# CutMonitor_PressureSensor.net
KiCad netlist of a schematic drawn in Altium Designer
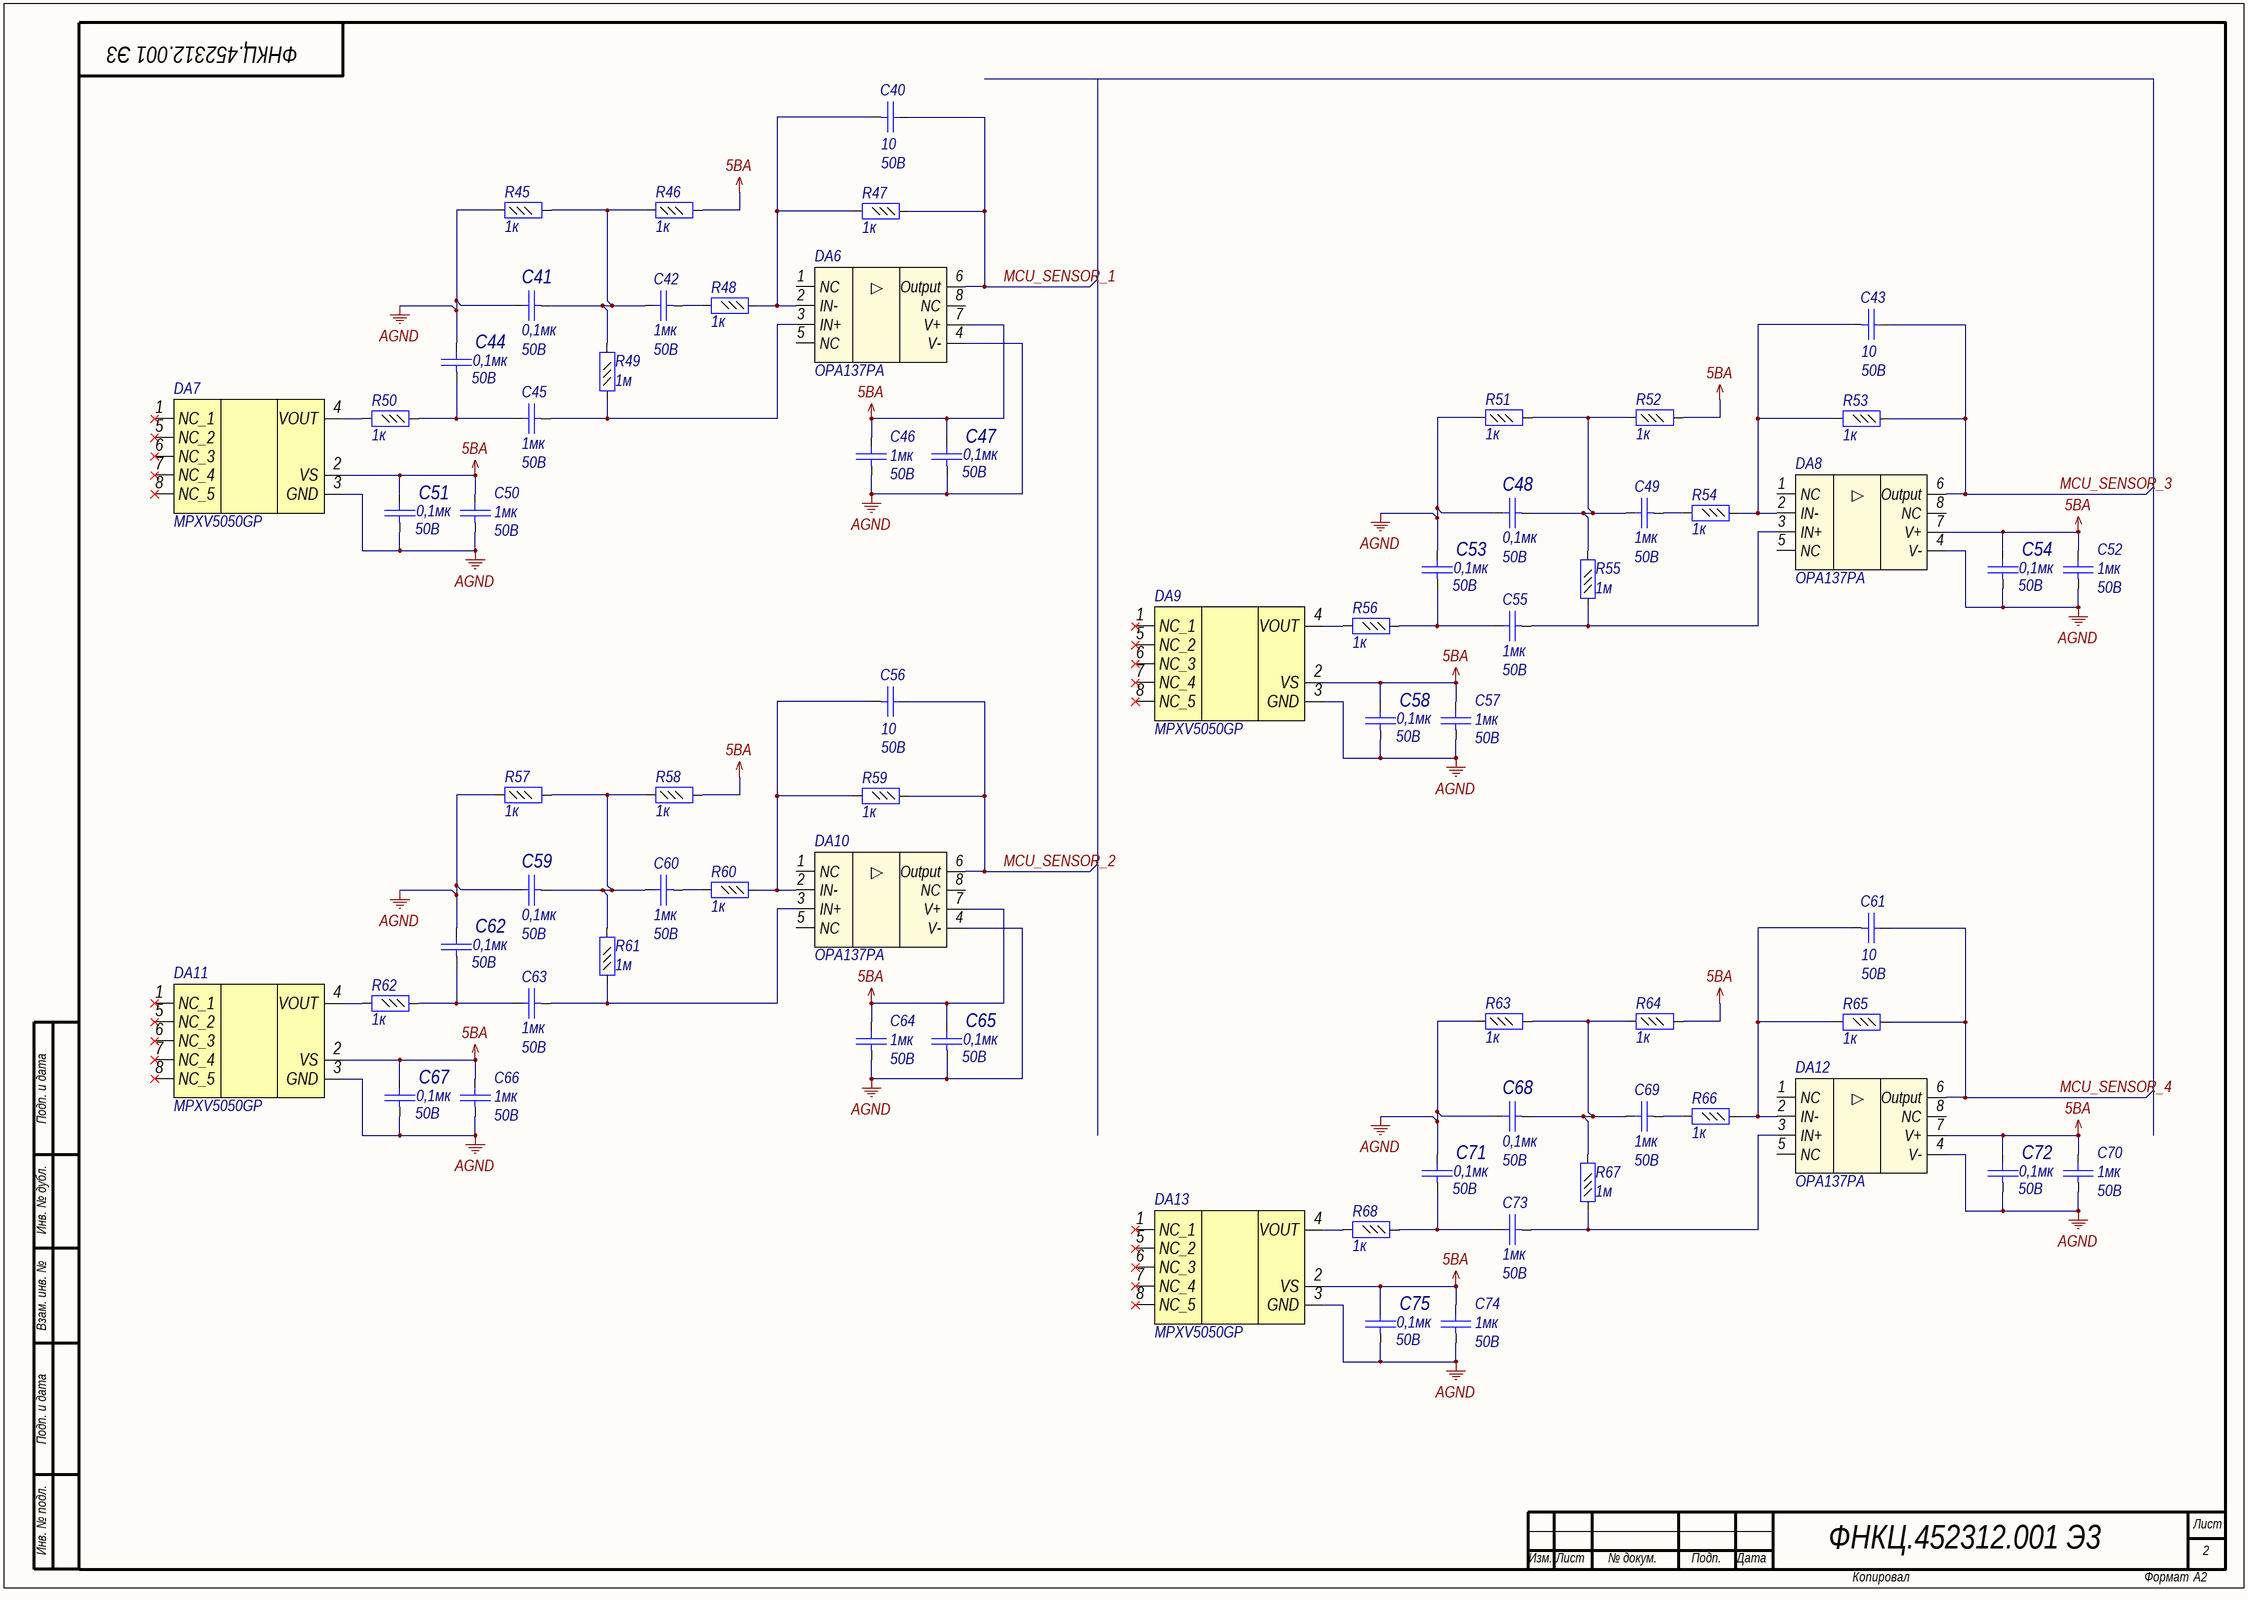
[diagram p0: CutMonitor_PressureSensor.SchDoc]

(export (version "E")
  (design (tool "Eeschema 10.0.6"))
  (components
    (comp (ref "C40")
      (value "10")
      (footprint "C0603")
      (description "Конденсатор")
      (fields
        (field (name "VOLTAGE") "50B")
        (field (name "PART NUMBER") "GRM1885C1H100J")
        (field (name "Comment") "Capacitor")
      )
      (libsource (lib "MOP44") (part "Capacitor"))
    )
    (comp (ref "C41")
      (value "0,1мк")
      (footprint "C0603")
      (description "Конденсатор")
      (fields
        (field (name "VOLTAGE") "50B")
        (field (name "PART NUMBER") "GRM188R71H104KA93D")
        (field (name "Comment") "Capacitor")
      )
      (libsource (lib "MOP44") (part "Capacitor"))
    )
    (comp (ref "C42")
      (value "1мк")
      (footprint "C0805")
      (description "Конденсатор")
      (fields
        (field (name "VOLTAGE") "50B")
        (field (name "PART NUMBER") "GRM21BR71H105K")
        (field (name "Comment") "Capacitor")
      )
      (libsource (lib "MOP44") (part "Capacitor"))
    )
    (comp (ref "C43")
      (value "10")
      (footprint "C0603")
      (description "Конденсатор")
      (fields
        (field (name "VOLTAGE") "50B")
        (field (name "PART NUMBER") "GRM1885C1H100J")
        (field (name "Comment") "Capacitor")
      )
      (libsource (lib "MOP44") (part "Capacitor"))
    )
    (comp (ref "C44")
      (value "0,1мк")
      (footprint "C0603")
      (description "Конденсатор")
      (fields
        (field (name "VOLTAGE") "50B")
        (field (name "PART NUMBER") "GRM188R71H104KA93D")
        (field (name "Comment") "Capacitor")
      )
      (libsource (lib "MOP44") (part "Capacitor"))
    )
    (comp (ref "C45")
      (value "1мк")
      (footprint "C0805")
      (description "Конденсатор")
      (fields
        (field (name "VOLTAGE") "50B")
        (field (name "PART NUMBER") "GRM21BR71H105K")
        (field (name "Comment") "Capacitor")
      )
      (libsource (lib "MOP44") (part "Capacitor"))
    )
    (comp (ref "C46")
      (value "1мк")
      (footprint "C0805")
      (description "Конденсатор")
      (fields
        (field (name "VOLTAGE") "50B")
        (field (name "PART NUMBER") "GRM21BR71H105K")
        (field (name "Comment") "Capacitor")
      )
      (libsource (lib "MOP44") (part "Capacitor"))
    )
    (comp (ref "C47")
      (value "0,1мк")
      (footprint "C0603")
      (description "Конденсатор")
      (fields
        (field (name "VOLTAGE") "50B")
        (field (name "PART NUMBER") "GRM188R71H104KA93D")
        (field (name "Comment") "Capacitor")
      )
      (libsource (lib "MOP44") (part "Capacitor"))
    )
    (comp (ref "C48")
      (value "0,1мк")
      (footprint "C0603")
      (description "Конденсатор")
      (fields
        (field (name "VOLTAGE") "50B")
        (field (name "PART NUMBER") "GRM188R71H104KA93D")
        (field (name "Comment") "Capacitor")
      )
      (libsource (lib "MOP44") (part "Capacitor"))
    )
    (comp (ref "C49")
      (value "1мк")
      (footprint "C0805")
      (description "Конденсатор")
      (fields
        (field (name "VOLTAGE") "50B")
        (field (name "PART NUMBER") "GRM21BR71H105K")
        (field (name "Comment") "Capacitor")
      )
      (libsource (lib "MOP44") (part "Capacitor"))
    )
    (comp (ref "C50")
      (value "1мк")
      (footprint "C0805")
      (description "Конденсатор")
      (fields
        (field (name "VOLTAGE") "50B")
        (field (name "PART NUMBER") "GRM21BR71H105K")
        (field (name "Comment") "Capacitor")
      )
      (libsource (lib "MOP44") (part "Capacitor"))
    )
    (comp (ref "C51")
      (value "0,1мк")
      (footprint "C0603")
      (description "Конденсатор")
      (fields
        (field (name "VOLTAGE") "50B")
        (field (name "PART NUMBER") "GRM188R71H104KA93D")
        (field (name "Comment") "Capacitor")
      )
      (libsource (lib "MOP44") (part "Capacitor"))
    )
    (comp (ref "C52")
      (value "1мк")
      (footprint "C0805")
      (description "Конденсатор")
      (fields
        (field (name "VOLTAGE") "50B")
        (field (name "PART NUMBER") "GRM21BR71H105K")
        (field (name "Comment") "Capacitor")
      )
      (libsource (lib "MOP44") (part "Capacitor"))
    )
    (comp (ref "C53")
      (value "0,1мк")
      (footprint "C0603")
      (description "Конденсатор")
      (fields
        (field (name "VOLTAGE") "50B")
        (field (name "PART NUMBER") "GRM188R71H104KA93D")
        (field (name "Comment") "Capacitor")
      )
      (libsource (lib "MOP44") (part "Capacitor"))
    )
    (comp (ref "C54")
      (value "0,1мк")
      (footprint "C0603")
      (description "Конденсатор")
      (fields
        (field (name "VOLTAGE") "50B")
        (field (name "PART NUMBER") "GRM188R71H104KA93D")
        (field (name "Comment") "Capacitor")
      )
      (libsource (lib "MOP44") (part "Capacitor"))
    )
    (comp (ref "C55")
      (value "1мк")
      (footprint "C0805")
      (description "Конденсатор")
      (fields
        (field (name "VOLTAGE") "50B")
        (field (name "PART NUMBER") "GRM21BR71H105K")
        (field (name "Comment") "Capacitor")
      )
      (libsource (lib "MOP44") (part "Capacitor"))
    )
    (comp (ref "C56")
      (value "10")
      (footprint "C0603")
      (description "Конденсатор")
      (fields
        (field (name "VOLTAGE") "50B")
        (field (name "PART NUMBER") "GRM1885C1H100J")
        (field (name "Comment") "Capacitor")
      )
      (libsource (lib "MOP44") (part "Capacitor"))
    )
    (comp (ref "C57")
      (value "1мк")
      (footprint "C0805")
      (description "Конденсатор")
      (fields
        (field (name "VOLTAGE") "50B")
        (field (name "PART NUMBER") "GRM21BR71H105K")
        (field (name "Comment") "Capacitor")
      )
      (libsource (lib "MOP44") (part "Capacitor"))
    )
    (comp (ref "C58")
      (value "0,1мк")
      (footprint "C0603")
      (description "Конденсатор")
      (fields
        (field (name "VOLTAGE") "50B")
        (field (name "PART NUMBER") "GRM188R71H104KA93D")
        (field (name "Comment") "Capacitor")
      )
      (libsource (lib "MOP44") (part "Capacitor"))
    )
    (comp (ref "C59")
      (value "0,1мк")
      (footprint "C0603")
      (description "Конденсатор")
      (fields
        (field (name "VOLTAGE") "50B")
        (field (name "PART NUMBER") "GRM188R71H104KA93D")
        (field (name "Comment") "Capacitor")
      )
      (libsource (lib "MOP44") (part "Capacitor"))
    )
    (comp (ref "C60")
      (value "1мк")
      (footprint "C0805")
      (description "Конденсатор")
      (fields
        (field (name "VOLTAGE") "50B")
        (field (name "PART NUMBER") "GRM21BR71H105K")
        (field (name "Comment") "Capacitor")
      )
      (libsource (lib "MOP44") (part "Capacitor"))
    )
    (comp (ref "C61")
      (value "10")
      (footprint "C0603")
      (description "Конденсатор")
      (fields
        (field (name "VOLTAGE") "50B")
        (field (name "PART NUMBER") "GRM1885C1H100J")
        (field (name "Comment") "Capacitor")
      )
      (libsource (lib "MOP44") (part "Capacitor"))
    )
    (comp (ref "C62")
      (value "0,1мк")
      (footprint "C0603")
      (description "Конденсатор")
      (fields
        (field (name "VOLTAGE") "50B")
        (field (name "PART NUMBER") "GRM188R71H104KA93D")
        (field (name "Comment") "Capacitor")
      )
      (libsource (lib "MOP44") (part "Capacitor"))
    )
    (comp (ref "C63")
      (value "1мк")
      (footprint "C0805")
      (description "Конденсатор")
      (fields
        (field (name "VOLTAGE") "50B")
        (field (name "PART NUMBER") "GRM21BR71H105K")
        (field (name "Comment") "Capacitor")
      )
      (libsource (lib "MOP44") (part "Capacitor"))
    )
    (comp (ref "C64")
      (value "1мк")
      (footprint "C0805")
      (description "Конденсатор")
      (fields
        (field (name "VOLTAGE") "50B")
        (field (name "PART NUMBER") "GRM21BR71H105K")
        (field (name "Comment") "Capacitor")
      )
      (libsource (lib "MOP44") (part "Capacitor"))
    )
    (comp (ref "C65")
      (value "0,1мк")
      (footprint "C0603")
      (description "Конденсатор")
      (fields
        (field (name "VOLTAGE") "50B")
        (field (name "PART NUMBER") "GRM188R71H104KA93D")
        (field (name "Comment") "Capacitor")
      )
      (libsource (lib "MOP44") (part "Capacitor"))
    )
    (comp (ref "C66")
      (value "1мк")
      (footprint "C0805")
      (description "Конденсатор")
      (fields
        (field (name "VOLTAGE") "50B")
        (field (name "PART NUMBER") "GRM21BR71H105K")
        (field (name "Comment") "Capacitor")
      )
      (libsource (lib "MOP44") (part "Capacitor"))
    )
    (comp (ref "C67")
      (value "0,1мк")
      (footprint "C0603")
      (description "Конденсатор")
      (fields
        (field (name "VOLTAGE") "50B")
        (field (name "PART NUMBER") "GRM188R71H104KA93D")
        (field (name "Comment") "Capacitor")
      )
      (libsource (lib "MOP44") (part "Capacitor"))
    )
    (comp (ref "C68")
      (value "0,1мк")
      (footprint "C0603")
      (description "Конденсатор")
      (fields
        (field (name "VOLTAGE") "50B")
        (field (name "PART NUMBER") "GRM188R71H104KA93D")
        (field (name "Comment") "Capacitor")
      )
      (libsource (lib "MOP44") (part "Capacitor"))
    )
    (comp (ref "C69")
      (value "1мк")
      (footprint "C0805")
      (description "Конденсатор")
      (fields
        (field (name "VOLTAGE") "50B")
        (field (name "PART NUMBER") "GRM21BR71H105K")
        (field (name "Comment") "Capacitor")
      )
      (libsource (lib "MOP44") (part "Capacitor"))
    )
    (comp (ref "C70")
      (value "1мк")
      (footprint "C0805")
      (description "Конденсатор")
      (fields
        (field (name "VOLTAGE") "50B")
        (field (name "PART NUMBER") "GRM21BR71H105K")
        (field (name "Comment") "Capacitor")
      )
      (libsource (lib "MOP44") (part "Capacitor"))
    )
    (comp (ref "C71")
      (value "0,1мк")
      (footprint "C0603")
      (description "Конденсатор")
      (fields
        (field (name "VOLTAGE") "50B")
        (field (name "PART NUMBER") "GRM188R71H104KA93D")
        (field (name "Comment") "Capacitor")
      )
      (libsource (lib "MOP44") (part "Capacitor"))
    )
    (comp (ref "C72")
      (value "0,1мк")
      (footprint "C0603")
      (description "Конденсатор")
      (fields
        (field (name "VOLTAGE") "50B")
        (field (name "PART NUMBER") "GRM188R71H104KA93D")
        (field (name "Comment") "Capacitor")
      )
      (libsource (lib "MOP44") (part "Capacitor"))
    )
    (comp (ref "C73")
      (value "1мк")
      (footprint "C0805")
      (description "Конденсатор")
      (fields
        (field (name "VOLTAGE") "50B")
        (field (name "PART NUMBER") "GRM21BR71H105K")
        (field (name "Comment") "Capacitor")
      )
      (libsource (lib "MOP44") (part "Capacitor"))
    )
    (comp (ref "C74")
      (value "1мк")
      (footprint "C0805")
      (description "Конденсатор")
      (fields
        (field (name "VOLTAGE") "50B")
        (field (name "PART NUMBER") "GRM21BR71H105K")
        (field (name "Comment") "Capacitor")
      )
      (libsource (lib "MOP44") (part "Capacitor"))
    )
    (comp (ref "C75")
      (value "0,1мк")
      (footprint "C0603")
      (description "Конденсатор")
      (fields
        (field (name "VOLTAGE") "50B")
        (field (name "PART NUMBER") "GRM188R71H104KA93D")
        (field (name "Comment") "Capacitor")
      )
      (libsource (lib "MOP44") (part "Capacitor"))
    )
    (comp (ref "DA6")
      (value "OPA137PA")
      (footprint "DIP8")
      (description "FET-INPUT OPERATIONAL AMPLIFIERS")
      (libsource (lib "MOP44") (part "OPA137PA"))
    )
    (comp (ref "DA7")
      (value "MPXV5050GP")
      (footprint "SOP8")
      (description "Integrated Silicon Pressure Sensor")
      (libsource (lib "MOP44") (part "MPXV5050GP"))
    )
    (comp (ref "DA8")
      (value "OPA137PA")
      (footprint "DIP8")
      (description "FET-INPUT OPERATIONAL AMPLIFIERS")
      (libsource (lib "MOP44") (part "OPA137PA"))
    )
    (comp (ref "DA9")
      (value "MPXV5050GP")
      (footprint "SOP8")
      (description "Integrated Silicon Pressure Sensor")
      (libsource (lib "MOP44") (part "MPXV5050GP"))
    )
    (comp (ref "DA10")
      (value "OPA137PA")
      (footprint "DIP8")
      (description "FET-INPUT OPERATIONAL AMPLIFIERS")
      (libsource (lib "MOP44") (part "OPA137PA"))
    )
    (comp (ref "DA11")
      (value "MPXV5050GP")
      (footprint "SOP8")
      (description "Integrated Silicon Pressure Sensor")
      (libsource (lib "MOP44") (part "MPXV5050GP"))
    )
    (comp (ref "DA12")
      (value "OPA137PA")
      (footprint "DIP8")
      (description "FET-INPUT OPERATIONAL AMPLIFIERS")
      (libsource (lib "MOP44") (part "OPA137PA"))
    )
    (comp (ref "DA13")
      (value "MPXV5050GP")
      (footprint "SOP8")
      (description "Integrated Silicon Pressure Sensor")
      (libsource (lib "MOP44") (part "MPXV5050GP"))
    )
    (comp (ref "R45")
      (value "1к")
      (footprint "R0603")
      (description "Резистор")
      (fields (field (name "PART NUMBER") "RC0603FR-071KL") (field (name "POWER") "0,062Вт"))
      (libsource (lib "") (part "Resistor_0,062Вт_2"))
    )
    (comp (ref "R46")
      (value "1к")
      (footprint "R0603")
      (description "Резистор")
      (fields (field (name "PART NUMBER") "RC0603FR-071KL") (field (name "POWER") "0,062Вт"))
      (libsource (lib "") (part "Resistor_0,062Вт_2"))
    )
    (comp (ref "R47")
      (value "1к")
      (footprint "R0603")
      (description "Резистор")
      (fields (field (name "PART NUMBER") "RC0603FR-071KL") (field (name "POWER") "0,062Вт"))
      (libsource (lib "") (part "Resistor_0,062Вт_1"))
    )
    (comp (ref "R48")
      (value "1к")
      (footprint "R0603")
      (description "Резистор")
      (fields (field (name "PART NUMBER") "RC0603FR-071KL") (field (name "POWER") "0,062Вт"))
      (libsource (lib "") (part "Resistor_0,062Вт_1"))
    )
    (comp (ref "R49")
      (value "1м")
      (footprint "R0603")
      (description "Резистор")
      (fields (field (name "PART NUMBER") "RC0603FR-071ML") (field (name "POWER") "0,062Вт"))
      (libsource (lib "MOP44") (part "Resistor_0,062Вт"))
    )
    (comp (ref "R50")
      (value "1к")
      (footprint "R0603")
      (description "Резистор")
      (fields (field (name "PART NUMBER") "RC0603FR-071KL") (field (name "POWER") "0,062Вт"))
      (libsource (lib "") (part "Resistor_0,062Вт_1"))
    )
    (comp (ref "R51")
      (value "1к")
      (footprint "R0603")
      (description "Резистор")
      (fields (field (name "PART NUMBER") "RC0603FR-071KL") (field (name "POWER") "0,062Вт"))
      (libsource (lib "") (part "Resistor_0,062Вт_2"))
    )
    (comp (ref "R52")
      (value "1к")
      (footprint "R0603")
      (description "Резистор")
      (fields (field (name "PART NUMBER") "RC0603FR-071KL") (field (name "POWER") "0,062Вт"))
      (libsource (lib "") (part "Resistor_0,062Вт_2"))
    )
    (comp (ref "R53")
      (value "1к")
      (footprint "R0603")
      (description "Резистор")
      (fields (field (name "PART NUMBER") "RC0603FR-071KL") (field (name "POWER") "0,062Вт"))
      (libsource (lib "") (part "Resistor_0,062Вт_1"))
    )
    (comp (ref "R54")
      (value "1к")
      (footprint "R0603")
      (description "Резистор")
      (fields (field (name "PART NUMBER") "RC0603FR-071KL") (field (name "POWER") "0,062Вт"))
      (libsource (lib "") (part "Resistor_0,062Вт_1"))
    )
    (comp (ref "R55")
      (value "1м")
      (footprint "R0603")
      (description "Резистор")
      (fields (field (name "PART NUMBER") "RC0603FR-071ML") (field (name "POWER") "0,062Вт"))
      (libsource (lib "MOP44") (part "Resistor_0,062Вт"))
    )
    (comp (ref "R56")
      (value "1к")
      (footprint "R0603")
      (description "Резистор")
      (fields (field (name "PART NUMBER") "RC0603FR-071KL") (field (name "POWER") "0,062Вт"))
      (libsource (lib "") (part "Resistor_0,062Вт_1"))
    )
    (comp (ref "R57")
      (value "1к")
      (footprint "R0603")
      (description "Резистор")
      (fields (field (name "PART NUMBER") "RC0603FR-071KL") (field (name "POWER") "0,062Вт"))
      (libsource (lib "") (part "Resistor_0,062Вт_2"))
    )
    (comp (ref "R58")
      (value "1к")
      (footprint "R0603")
      (description "Резистор")
      (fields (field (name "PART NUMBER") "RC0603FR-071KL") (field (name "POWER") "0,062Вт"))
      (libsource (lib "") (part "Resistor_0,062Вт_2"))
    )
    (comp (ref "R59")
      (value "1к")
      (footprint "R0603")
      (description "Резистор")
      (fields (field (name "PART NUMBER") "RC0603FR-071KL") (field (name "POWER") "0,062Вт"))
      (libsource (lib "") (part "Resistor_0,062Вт_1"))
    )
    (comp (ref "R60")
      (value "1к")
      (footprint "R0603")
      (description "Резистор")
      (fields (field (name "PART NUMBER") "RC0603FR-071KL") (field (name "POWER") "0,062Вт"))
      (libsource (lib "") (part "Resistor_0,062Вт_1"))
    )
    (comp (ref "R61")
      (value "1м")
      (footprint "R0603")
      (description "Резистор")
      (fields (field (name "PART NUMBER") "RC0603FR-071ML") (field (name "POWER") "0,062Вт"))
      (libsource (lib "MOP44") (part "Resistor_0,062Вт"))
    )
    (comp (ref "R62")
      (value "1к")
      (footprint "R0603")
      (description "Резистор")
      (fields (field (name "PART NUMBER") "RC0603FR-071KL") (field (name "POWER") "0,062Вт"))
      (libsource (lib "") (part "Resistor_0,062Вт_1"))
    )
    (comp (ref "R63")
      (value "1к")
      (footprint "R0603")
      (description "Резистор")
      (fields (field (name "PART NUMBER") "RC0603FR-071KL") (field (name "POWER") "0,062Вт"))
      (libsource (lib "") (part "Resistor_0,062Вт_2"))
    )
    (comp (ref "R64")
      (value "1к")
      (footprint "R0603")
      (description "Резистор")
      (fields (field (name "PART NUMBER") "RC0603FR-071KL") (field (name "POWER") "0,062Вт"))
      (libsource (lib "") (part "Resistor_0,062Вт_2"))
    )
    (comp (ref "R65")
      (value "1к")
      (footprint "R0603")
      (description "Резистор")
      (fields (field (name "PART NUMBER") "RC0603FR-071KL") (field (name "POWER") "0,062Вт"))
      (libsource (lib "") (part "Resistor_0,062Вт_1"))
    )
    (comp (ref "R66")
      (value "1к")
      (footprint "R0603")
      (description "Резистор")
      (fields (field (name "PART NUMBER") "RC0603FR-071KL") (field (name "POWER") "0,062Вт"))
      (libsource (lib "") (part "Resistor_0,062Вт_1"))
    )
    (comp (ref "R67")
      (value "1м")
      (footprint "R0603")
      (description "Резистор")
      (fields (field (name "PART NUMBER") "RC0603FR-071ML") (field (name "POWER") "0,062Вт"))
      (libsource (lib "MOP44") (part "Resistor_0,062Вт"))
    )
    (comp (ref "R68")
      (value "1к")
      (footprint "R0603")
      (description "Резистор")
      (fields (field (name "PART NUMBER") "RC0603FR-071KL") (field (name "POWER") "0,062Вт"))
      (libsource (lib "") (part "Resistor_0,062Вт_1"))
    )
  )
  (nets
    (net (code "1") (name "/MCU_SENSOR_1") (class "Default")
      (node (ref "C40") (pin "2") (pinfunction "2_2") (pintype "passive"))
      (node (ref "DA6") (pin "6") (pinfunction "Output_6") (pintype "power_in"))
      (node (ref "R47") (pin "1") (pinfunction "1_1") (pintype "passive"))
    )
    (net (code "2") (name "/MCU_SENSOR_2") (class "Default")
      (node (ref "C56") (pin "2") (pinfunction "2_2") (pintype "passive"))
      (node (ref "DA10") (pin "6") (pinfunction "Output_6") (pintype "power_in"))
      (node (ref "R59") (pin "1") (pinfunction "1_1") (pintype "passive"))
    )
    (net (code "3") (name "/MCU_SENSOR_3") (class "Default")
      (node (ref "C43") (pin "2") (pinfunction "2_2") (pintype "passive"))
      (node (ref "DA8") (pin "6") (pinfunction "Output_6") (pintype "power_in"))
      (node (ref "R53") (pin "1") (pinfunction "1_1") (pintype "passive"))
    )
    (net (code "4") (name "/MCU_SENSOR_4") (class "Default")
      (node (ref "C61") (pin "2") (pinfunction "2_2") (pintype "passive"))
      (node (ref "DA12") (pin "6") (pinfunction "Output_6") (pintype "power_in"))
      (node (ref "R65") (pin "1") (pinfunction "1_1") (pintype "passive"))
    )
    (net (code "5") (name "5BA") (class "Default")
      (node (ref "C46") (pin "2") (pinfunction "2_2") (pintype "passive"))
      (node (ref "C47") (pin "2") (pinfunction "2_2") (pintype "passive"))
      (node (ref "C50") (pin "2") (pinfunction "2_2") (pintype "passive"))
      (node (ref "C51") (pin "2") (pinfunction "2_2") (pintype "passive"))
      (node (ref "C52") (pin "2") (pinfunction "2_2") (pintype "passive"))
      (node (ref "C54") (pin "2") (pinfunction "2_2") (pintype "passive"))
      (node (ref "C57") (pin "2") (pinfunction "2_2") (pintype "passive"))
      (node (ref "C58") (pin "2") (pinfunction "2_2") (pintype "passive"))
      (node (ref "C64") (pin "2") (pinfunction "2_2") (pintype "passive"))
      (node (ref "C65") (pin "2") (pinfunction "2_2") (pintype "passive"))
      (node (ref "C66") (pin "2") (pinfunction "2_2") (pintype "passive"))
      (node (ref "C67") (pin "2") (pinfunction "2_2") (pintype "passive"))
      (node (ref "C70") (pin "2") (pinfunction "2_2") (pintype "passive"))
      (node (ref "C72") (pin "2") (pinfunction "2_2") (pintype "passive"))
      (node (ref "C74") (pin "2") (pinfunction "2_2") (pintype "passive"))
      (node (ref "C75") (pin "2") (pinfunction "2_2") (pintype "passive"))
      (node (ref "DA10") (pin "7") (pinfunction "V+_7") (pintype "power_in"))
      (node (ref "DA11") (pin "2") (pinfunction "VS_2") (pintype "passive"))
      (node (ref "DA12") (pin "7") (pinfunction "V+_7") (pintype "power_in"))
      (node (ref "DA13") (pin "2") (pinfunction "VS_2") (pintype "passive"))
      (node (ref "DA6") (pin "7") (pinfunction "V+_7") (pintype "power_in"))
      (node (ref "DA7") (pin "2") (pinfunction "VS_2") (pintype "passive"))
      (node (ref "DA8") (pin "7") (pinfunction "V+_7") (pintype "power_in"))
      (node (ref "DA9") (pin "2") (pinfunction "VS_2") (pintype "passive"))
      (node (ref "R46") (pin "2") (pinfunction "2_2") (pintype "passive"))
      (node (ref "R52") (pin "2") (pinfunction "2_2") (pintype "passive"))
      (node (ref "R58") (pin "2") (pinfunction "2_2") (pintype "passive"))
      (node (ref "R64") (pin "2") (pinfunction "2_2") (pintype "passive"))
    )
    (net (code "6") (name "AGND") (class "Default")
      (node (ref "C41") (pin "2") (pinfunction "2_2") (pintype "passive"))
      (node (ref "C44") (pin "2") (pinfunction "2_2") (pintype "passive"))
      (node (ref "C46") (pin "1") (pinfunction "1_1") (pintype "passive"))
      (node (ref "C47") (pin "1") (pinfunction "1_1") (pintype "passive"))
      (node (ref "C48") (pin "2") (pinfunction "2_2") (pintype "passive"))
      (node (ref "C50") (pin "1") (pinfunction "1_1") (pintype "passive"))
      (node (ref "C51") (pin "1") (pinfunction "1_1") (pintype "passive"))
      (node (ref "C52") (pin "1") (pinfunction "1_1") (pintype "passive"))
      (node (ref "C53") (pin "2") (pinfunction "2_2") (pintype "passive"))
      (node (ref "C54") (pin "1") (pinfunction "1_1") (pintype "passive"))
      (node (ref "C57") (pin "1") (pinfunction "1_1") (pintype "passive"))
      (node (ref "C58") (pin "1") (pinfunction "1_1") (pintype "passive"))
      (node (ref "C59") (pin "2") (pinfunction "2_2") (pintype "passive"))
      (node (ref "C62") (pin "2") (pinfunction "2_2") (pintype "passive"))
      (node (ref "C64") (pin "1") (pinfunction "1_1") (pintype "passive"))
      (node (ref "C65") (pin "1") (pinfunction "1_1") (pintype "passive"))
      (node (ref "C66") (pin "1") (pinfunction "1_1") (pintype "passive"))
      (node (ref "C67") (pin "1") (pinfunction "1_1") (pintype "passive"))
      (node (ref "C68") (pin "2") (pinfunction "2_2") (pintype "passive"))
      (node (ref "C70") (pin "1") (pinfunction "1_1") (pintype "passive"))
      (node (ref "C71") (pin "2") (pinfunction "2_2") (pintype "passive"))
      (node (ref "C72") (pin "1") (pinfunction "1_1") (pintype "passive"))
      (node (ref "C74") (pin "1") (pinfunction "1_1") (pintype "passive"))
      (node (ref "C75") (pin "1") (pinfunction "1_1") (pintype "passive"))
      (node (ref "DA10") (pin "4") (pinfunction "V-_4") (pintype "power_in"))
      (node (ref "DA11") (pin "3") (pinfunction "GND_3") (pintype "passive"))
      (node (ref "DA12") (pin "4") (pinfunction "V-_4") (pintype "power_in"))
      (node (ref "DA13") (pin "3") (pinfunction "GND_3") (pintype "passive"))
      (node (ref "DA6") (pin "4") (pinfunction "V-_4") (pintype "power_in"))
      (node (ref "DA7") (pin "3") (pinfunction "GND_3") (pintype "passive"))
      (node (ref "DA8") (pin "4") (pinfunction "V-_4") (pintype "power_in"))
      (node (ref "DA9") (pin "3") (pinfunction "GND_3") (pintype "passive"))
      (node (ref "R45") (pin "1") (pinfunction "1_1") (pintype "passive"))
      (node (ref "R51") (pin "1") (pinfunction "1_1") (pintype "passive"))
      (node (ref "R57") (pin "1") (pinfunction "1_1") (pintype "passive"))
      (node (ref "R63") (pin "1") (pinfunction "1_1") (pintype "passive"))
    )
    (net (code "7") (name "Net-(C41-Pad1)") (class "Default")
      (node (ref "C41") (pin "1") (pinfunction "1_1") (pintype "passive"))
      (node (ref "C42") (pin "2") (pinfunction "2_2") (pintype "passive"))
      (node (ref "R45") (pin "2") (pinfunction "2_2") (pintype "passive"))
      (node (ref "R46") (pin "1") (pinfunction "1_1") (pintype "passive"))
      (node (ref "R49") (pin "2") (pinfunction "2_2") (pintype "passive"))
    )
    (net (code "8") (name "Net-(C42-Pad1)") (class "Default")
      (node (ref "C42") (pin "1") (pinfunction "1_1") (pintype "passive"))
      (node (ref "R48") (pin "2") (pinfunction "2_2") (pintype "passive"))
    )
    (net (code "9") (name "Net-(C44-Pad1)") (class "Default")
      (node (ref "C44") (pin "1") (pinfunction "1_1") (pintype "passive"))
      (node (ref "C45") (pin "2") (pinfunction "2_2") (pintype "passive"))
      (node (ref "R50") (pin "1") (pinfunction "1_1") (pintype "passive"))
    )
    (net (code "10") (name "Net-(C48-Pad1)") (class "Default")
      (node (ref "C48") (pin "1") (pinfunction "1_1") (pintype "passive"))
      (node (ref "C49") (pin "2") (pinfunction "2_2") (pintype "passive"))
      (node (ref "R51") (pin "2") (pinfunction "2_2") (pintype "passive"))
      (node (ref "R52") (pin "1") (pinfunction "1_1") (pintype "passive"))
      (node (ref "R55") (pin "2") (pinfunction "2_2") (pintype "passive"))
    )
    (net (code "11") (name "Net-(C49-Pad1)") (class "Default")
      (node (ref "C49") (pin "1") (pinfunction "1_1") (pintype "passive"))
      (node (ref "R54") (pin "2") (pinfunction "2_2") (pintype "passive"))
    )
    (net (code "12") (name "Net-(C53-Pad1)") (class "Default")
      (node (ref "C53") (pin "1") (pinfunction "1_1") (pintype "passive"))
      (node (ref "C55") (pin "2") (pinfunction "2_2") (pintype "passive"))
      (node (ref "R56") (pin "1") (pinfunction "1_1") (pintype "passive"))
    )
    (net (code "13") (name "Net-(C59-Pad1)") (class "Default")
      (node (ref "C59") (pin "1") (pinfunction "1_1") (pintype "passive"))
      (node (ref "C60") (pin "2") (pinfunction "2_2") (pintype "passive"))
      (node (ref "R57") (pin "2") (pinfunction "2_2") (pintype "passive"))
      (node (ref "R58") (pin "1") (pinfunction "1_1") (pintype "passive"))
      (node (ref "R61") (pin "2") (pinfunction "2_2") (pintype "passive"))
    )
    (net (code "14") (name "Net-(C60-Pad1)") (class "Default")
      (node (ref "C60") (pin "1") (pinfunction "1_1") (pintype "passive"))
      (node (ref "R60") (pin "2") (pinfunction "2_2") (pintype "passive"))
    )
    (net (code "15") (name "Net-(C62-Pad1)") (class "Default")
      (node (ref "C62") (pin "1") (pinfunction "1_1") (pintype "passive"))
      (node (ref "C63") (pin "2") (pinfunction "2_2") (pintype "passive"))
      (node (ref "R62") (pin "1") (pinfunction "1_1") (pintype "passive"))
    )
    (net (code "16") (name "Net-(C68-Pad1)") (class "Default")
      (node (ref "C68") (pin "1") (pinfunction "1_1") (pintype "passive"))
      (node (ref "C69") (pin "2") (pinfunction "2_2") (pintype "passive"))
      (node (ref "R63") (pin "2") (pinfunction "2_2") (pintype "passive"))
      (node (ref "R64") (pin "1") (pinfunction "1_1") (pintype "passive"))
      (node (ref "R67") (pin "2") (pinfunction "2_2") (pintype "passive"))
    )
    (net (code "17") (name "Net-(C69-Pad1)") (class "Default")
      (node (ref "C69") (pin "1") (pinfunction "1_1") (pintype "passive"))
      (node (ref "R66") (pin "2") (pinfunction "2_2") (pintype "passive"))
    )
    (net (code "18") (name "Net-(C71-Pad1)") (class "Default")
      (node (ref "C71") (pin "1") (pinfunction "1_1") (pintype "passive"))
      (node (ref "C73") (pin "2") (pinfunction "2_2") (pintype "passive"))
      (node (ref "R68") (pin "1") (pinfunction "1_1") (pintype "passive"))
    )
    (net (code "19") (name "Net-(DA6-IN+)") (class "Default")
      (node (ref "C45") (pin "1") (pinfunction "1_1") (pintype "passive"))
      (node (ref "DA6") (pin "3") (pinfunction "IN+_3") (pintype "power_in"))
      (node (ref "R49") (pin "1") (pinfunction "1_1") (pintype "passive"))
    )
    (net (code "20") (name "Net-(DA6-IN-)") (class "Default")
      (node (ref "C40") (pin "1") (pinfunction "1_1") (pintype "passive"))
      (node (ref "DA6") (pin "2") (pinfunction "IN-_2") (pintype "power_in"))
      (node (ref "R47") (pin "2") (pinfunction "2_2") (pintype "passive"))
      (node (ref "R48") (pin "1") (pinfunction "1_1") (pintype "passive"))
    )
    (net (code "21") (name "Net-(DA7-VOUT)") (class "Default")
      (node (ref "DA7") (pin "4") (pinfunction "VOUT_4") (pintype "passive"))
      (node (ref "R50") (pin "2") (pinfunction "2_2") (pintype "passive"))
    )
    (net (code "22") (name "Net-(DA8-IN+)") (class "Default")
      (node (ref "C55") (pin "1") (pinfunction "1_1") (pintype "passive"))
      (node (ref "DA8") (pin "3") (pinfunction "IN+_3") (pintype "power_in"))
      (node (ref "R55") (pin "1") (pinfunction "1_1") (pintype "passive"))
    )
    (net (code "23") (name "Net-(DA8-IN-)") (class "Default")
      (node (ref "C43") (pin "1") (pinfunction "1_1") (pintype "passive"))
      (node (ref "DA8") (pin "2") (pinfunction "IN-_2") (pintype "power_in"))
      (node (ref "R53") (pin "2") (pinfunction "2_2") (pintype "passive"))
      (node (ref "R54") (pin "1") (pinfunction "1_1") (pintype "passive"))
    )
    (net (code "24") (name "Net-(DA9-VOUT)") (class "Default")
      (node (ref "DA9") (pin "4") (pinfunction "VOUT_4") (pintype "passive"))
      (node (ref "R56") (pin "2") (pinfunction "2_2") (pintype "passive"))
    )
    (net (code "25") (name "Net-(DA10-IN+)") (class "Default")
      (node (ref "C63") (pin "1") (pinfunction "1_1") (pintype "passive"))
      (node (ref "DA10") (pin "3") (pinfunction "IN+_3") (pintype "power_in"))
      (node (ref "R61") (pin "1") (pinfunction "1_1") (pintype "passive"))
    )
    (net (code "26") (name "Net-(DA10-IN-)") (class "Default")
      (node (ref "C56") (pin "1") (pinfunction "1_1") (pintype "passive"))
      (node (ref "DA10") (pin "2") (pinfunction "IN-_2") (pintype "power_in"))
      (node (ref "R59") (pin "2") (pinfunction "2_2") (pintype "passive"))
      (node (ref "R60") (pin "1") (pinfunction "1_1") (pintype "passive"))
    )
    (net (code "27") (name "Net-(DA11-VOUT)") (class "Default")
      (node (ref "DA11") (pin "4") (pinfunction "VOUT_4") (pintype "passive"))
      (node (ref "R62") (pin "2") (pinfunction "2_2") (pintype "passive"))
    )
    (net (code "28") (name "Net-(DA12-IN+)") (class "Default")
      (node (ref "C73") (pin "1") (pinfunction "1_1") (pintype "passive"))
      (node (ref "DA12") (pin "3") (pinfunction "IN+_3") (pintype "power_in"))
      (node (ref "R67") (pin "1") (pinfunction "1_1") (pintype "passive"))
    )
    (net (code "29") (name "Net-(DA12-IN-)") (class "Default")
      (node (ref "C61") (pin "1") (pinfunction "1_1") (pintype "passive"))
      (node (ref "DA12") (pin "2") (pinfunction "IN-_2") (pintype "power_in"))
      (node (ref "R65") (pin "2") (pinfunction "2_2") (pintype "passive"))
      (node (ref "R66") (pin "1") (pinfunction "1_1") (pintype "passive"))
    )
    (net (code "30") (name "Net-(DA13-VOUT)") (class "Default")
      (node (ref "DA13") (pin "4") (pinfunction "VOUT_4") (pintype "passive"))
      (node (ref "R68") (pin "2") (pinfunction "2_2") (pintype "passive"))
    )
    (net (code "31") (name "unconnected-(DA6-NC-Pad1)") (class "Default")
      (node (ref "DA6") (pin "1") (pinfunction "NC_1") (pintype "power_in"))
    )
    (net (code "32") (name "unconnected-(DA6-NC-Pad5)") (class "Default")
      (node (ref "DA6") (pin "5") (pinfunction "NC_5") (pintype "power_in"))
    )
    (net (code "33") (name "unconnected-(DA6-NC-Pad8)") (class "Default")
      (node (ref "DA6") (pin "8") (pinfunction "NC_8") (pintype "power_in"))
    )
    (net (code "34") (name "unconnected-(DA7-NC_1-Pad1)") (class "Default")
      (node (ref "DA7") (pin "1") (pinfunction "NC_1_1") (pintype "passive+no_connect"))
    )
    (net (code "35") (name "unconnected-(DA7-NC_2-Pad5)") (class "Default")
      (node (ref "DA7") (pin "5") (pinfunction "NC_2_5") (pintype "passive+no_connect"))
    )
    (net (code "36") (name "unconnected-(DA7-NC_3-Pad6)") (class "Default")
      (node (ref "DA7") (pin "6") (pinfunction "NC_3_6") (pintype "passive+no_connect"))
    )
    (net (code "37") (name "unconnected-(DA7-NC_4-Pad7)") (class "Default")
      (node (ref "DA7") (pin "7") (pinfunction "NC_4_7") (pintype "passive+no_connect"))
    )
    (net (code "38") (name "unconnected-(DA7-NC_5-Pad8)") (class "Default")
      (node (ref "DA7") (pin "8") (pinfunction "NC_5_8") (pintype "passive+no_connect"))
    )
    (net (code "39") (name "unconnected-(DA8-NC-Pad1)") (class "Default")
      (node (ref "DA8") (pin "1") (pinfunction "NC_1") (pintype "power_in"))
    )
    (net (code "40") (name "unconnected-(DA8-NC-Pad5)") (class "Default")
      (node (ref "DA8") (pin "5") (pinfunction "NC_5") (pintype "power_in"))
    )
    (net (code "41") (name "unconnected-(DA8-NC-Pad8)") (class "Default")
      (node (ref "DA8") (pin "8") (pinfunction "NC_8") (pintype "power_in"))
    )
    (net (code "42") (name "unconnected-(DA9-NC_1-Pad1)") (class "Default")
      (node (ref "DA9") (pin "1") (pinfunction "NC_1_1") (pintype "passive+no_connect"))
    )
    (net (code "43") (name "unconnected-(DA9-NC_2-Pad5)") (class "Default")
      (node (ref "DA9") (pin "5") (pinfunction "NC_2_5") (pintype "passive+no_connect"))
    )
    (net (code "44") (name "unconnected-(DA9-NC_3-Pad6)") (class "Default")
      (node (ref "DA9") (pin "6") (pinfunction "NC_3_6") (pintype "passive+no_connect"))
    )
    (net (code "45") (name "unconnected-(DA9-NC_4-Pad7)") (class "Default")
      (node (ref "DA9") (pin "7") (pinfunction "NC_4_7") (pintype "passive+no_connect"))
    )
    (net (code "46") (name "unconnected-(DA9-NC_5-Pad8)") (class "Default")
      (node (ref "DA9") (pin "8") (pinfunction "NC_5_8") (pintype "passive+no_connect"))
    )
    (net (code "47") (name "unconnected-(DA10-NC-Pad1)") (class "Default")
      (node (ref "DA10") (pin "1") (pinfunction "NC_1") (pintype "power_in"))
    )
    (net (code "48") (name "unconnected-(DA10-NC-Pad5)") (class "Default")
      (node (ref "DA10") (pin "5") (pinfunction "NC_5") (pintype "power_in"))
    )
    (net (code "49") (name "unconnected-(DA10-NC-Pad8)") (class "Default")
      (node (ref "DA10") (pin "8") (pinfunction "NC_8") (pintype "power_in"))
    )
    (net (code "50") (name "unconnected-(DA11-NC_1-Pad1)") (class "Default")
      (node (ref "DA11") (pin "1") (pinfunction "NC_1_1") (pintype "passive+no_connect"))
    )
    (net (code "51") (name "unconnected-(DA11-NC_2-Pad5)") (class "Default")
      (node (ref "DA11") (pin "5") (pinfunction "NC_2_5") (pintype "passive+no_connect"))
    )
    (net (code "52") (name "unconnected-(DA11-NC_3-Pad6)") (class "Default")
      (node (ref "DA11") (pin "6") (pinfunction "NC_3_6") (pintype "passive+no_connect"))
    )
    (net (code "53") (name "unconnected-(DA11-NC_4-Pad7)") (class "Default")
      (node (ref "DA11") (pin "7") (pinfunction "NC_4_7") (pintype "passive+no_connect"))
    )
    (net (code "54") (name "unconnected-(DA11-NC_5-Pad8)") (class "Default")
      (node (ref "DA11") (pin "8") (pinfunction "NC_5_8") (pintype "passive+no_connect"))
    )
    (net (code "55") (name "unconnected-(DA12-NC-Pad1)") (class "Default")
      (node (ref "DA12") (pin "1") (pinfunction "NC_1") (pintype "power_in"))
    )
    (net (code "56") (name "unconnected-(DA12-NC-Pad5)") (class "Default")
      (node (ref "DA12") (pin "5") (pinfunction "NC_5") (pintype "power_in"))
    )
    (net (code "57") (name "unconnected-(DA12-NC-Pad8)") (class "Default")
      (node (ref "DA12") (pin "8") (pinfunction "NC_8") (pintype "power_in"))
    )
    (net (code "58") (name "unconnected-(DA13-NC_1-Pad1)") (class "Default")
      (node (ref "DA13") (pin "1") (pinfunction "NC_1_1") (pintype "passive+no_connect"))
    )
    (net (code "59") (name "unconnected-(DA13-NC_2-Pad5)") (class "Default")
      (node (ref "DA13") (pin "5") (pinfunction "NC_2_5") (pintype "passive+no_connect"))
    )
    (net (code "60") (name "unconnected-(DA13-NC_3-Pad6)") (class "Default")
      (node (ref "DA13") (pin "6") (pinfunction "NC_3_6") (pintype "passive+no_connect"))
    )
    (net (code "61") (name "unconnected-(DA13-NC_4-Pad7)") (class "Default")
      (node (ref "DA13") (pin "7") (pinfunction "NC_4_7") (pintype "passive+no_connect"))
    )
    (net (code "62") (name "unconnected-(DA13-NC_5-Pad8)") (class "Default")
      (node (ref "DA13") (pin "8") (pinfunction "NC_5_8") (pintype "passive+no_connect"))
    )
  )
)
